# series_parallel_examples3.net
KiCad netlist of a schematic drawn in EAGLE
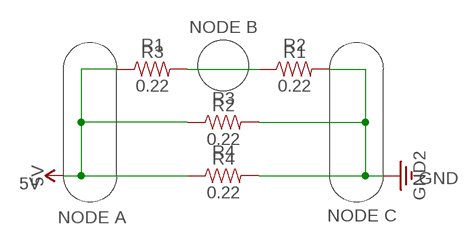
[diagram p0: schematic, sheet 1]

(export (version "E")
  (design (tool "Eeschema 10.0.6"))
  (components
    (comp (ref "R1")
      (value "0.22")
      (footprint "eagle-import:0805")
      (libsource (lib "eagle-import") (part "0.22OHM-0805-1/4W-1%"))
    )
    (comp (ref "R2")
      (value "0.22")
      (footprint "eagle-import:0805")
      (libsource (lib "eagle-import") (part "0.22OHM-0805-1/4W-1%"))
    )
    (comp (ref "R3")
      (value "0.22")
      (footprint "eagle-import:0805")
      (libsource (lib "eagle-import") (part "0.22OHM-0805-1/4W-1%"))
    )
    (comp (ref "R4")
      (value "0.22")
      (footprint "eagle-import:0805")
      (libsource (lib "eagle-import") (part "0.22OHM-0805-1/4W-1%"))
    )
  )
  (nets
    (net (code "1") (name "5V") (class "Default")
      (node (ref "R2") (pin "1") (pinfunction "1_1") (pintype "passive"))
      (node (ref "R3") (pin "1") (pinfunction "1_1") (pintype "passive"))
      (node (ref "R4") (pin "1") (pinfunction "1_1") (pintype "passive"))
    )
    (net (code "2") (name "GND2") (class "Default")
      (node (ref "R1") (pin "2") (pinfunction "2_2") (pintype "passive"))
      (node (ref "R2") (pin "2") (pinfunction "2_2") (pintype "passive"))
      (node (ref "R4") (pin "2") (pinfunction "2_2") (pintype "passive"))
    )
    (net (code "3") (name "Net-(R1-Pad1)") (class "Default")
      (node (ref "R1") (pin "1") (pinfunction "1_1") (pintype "passive"))
      (node (ref "R3") (pin "2") (pinfunction "2_2") (pintype "passive"))
    )
  )
)
